# xiaozhi.net
KiCad netlist of a schematic drawn in EasyEDA Pro
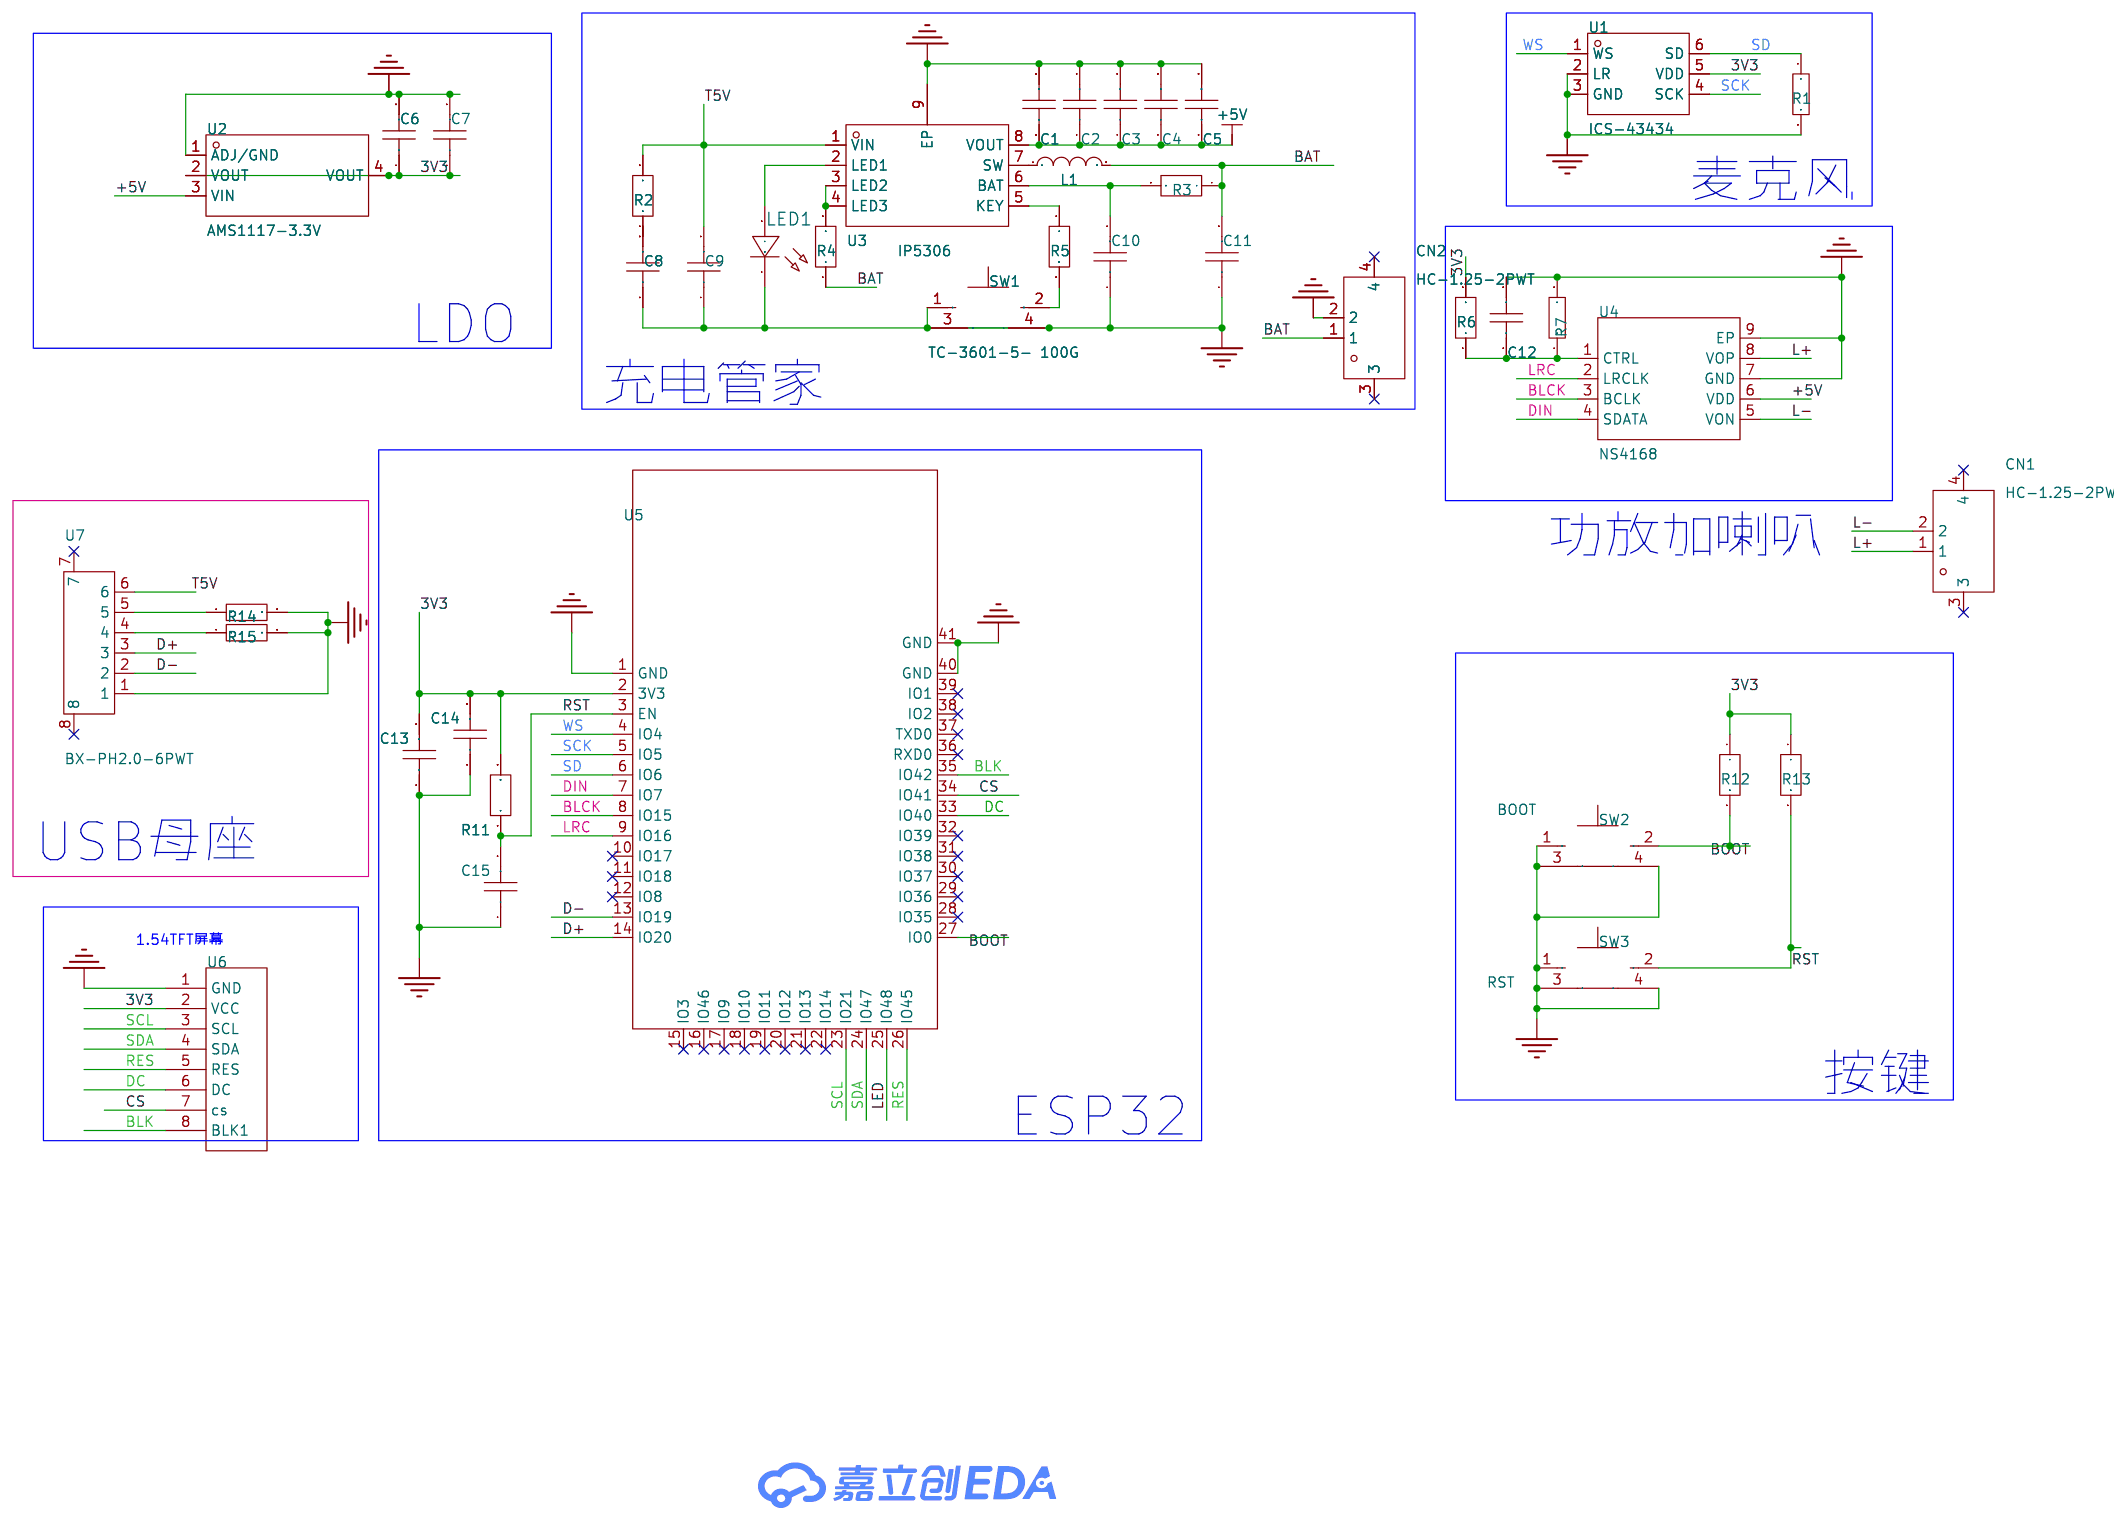
[diagram p0: schematic sheet]

(export (version "E")
  (design (tool "Eeschema 10.0.6"))
  (components
    (comp (ref "C1")
      (value "22UF")
      (footprint "easyedapro:C0603")
      (libsource (lib "easyedapro") (part "CapAcitance"))
    )
    (comp (ref "C2")
      (value "22UF")
      (footprint "easyedapro:C0603")
      (libsource (lib "easyedapro") (part "CapAcitance"))
    )
    (comp (ref "C3")
      (value "22UF")
      (footprint "easyedapro:C0603")
      (libsource (lib "easyedapro") (part "CapAcitance"))
    )
    (comp (ref "C4")
      (value "22UF")
      (footprint "easyedapro:C0603")
      (libsource (lib "easyedapro") (part "CapAcitance"))
    )
    (comp (ref "C5")
      (value "22UF")
      (footprint "easyedapro:C0603")
      (libsource (lib "easyedapro") (part "CapAcitance"))
    )
    (comp (ref "C6")
      (value "100NF")
      (footprint "easyedapro:C0603")
      (libsource (lib "easyedapro") (part "CapAcitance"))
    )
    (comp (ref "C7")
      (value "10UF")
      (footprint "easyedapro:C0603")
      (libsource (lib "easyedapro") (part "CapAcitance"))
    )
    (comp (ref "C8")
      (value "10uF")
      (footprint "easyedapro:C0805")
      (description "容值:10uF;精度:±10%;额定电压:25V;温度系数:X5R;")
      (fields
        (field (name "Manufacturer Part") "CGA0805X5R106K250MT")
        (field (name "Manufacturer") "HRE(芯声)")
      )
      (libsource (lib "easyedapro") (part "CGA0805X5R106K250MT"))
    )
    (comp (ref "C9")
      (value "10uF")
      (footprint "easyedapro:C0805")
      (description "容值:10uF;精度:±10%;额定电压:25V;温度系数:X5R;")
      (fields
        (field (name "Manufacturer Part") "CGA0805X5R106K250MT")
        (field (name "Manufacturer") "HRE(芯声)")
      )
      (libsource (lib "easyedapro") (part "CGA0805X5R106K250MT"))
    )
    (comp (ref "C10")
      (value "22UF")
      (footprint "easyedapro:C0603")
      (libsource (lib "easyedapro") (part "CapAcitance"))
    )
    (comp (ref "C11")
      (value "22UF")
      (footprint "easyedapro:C0603")
      (libsource (lib "easyedapro") (part "CapAcitance"))
    )
    (comp (ref "C12")
      (value "10UF")
      (footprint "easyedapro:C0603")
      (libsource (lib "easyedapro") (part "CapAcitance"))
    )
    (comp (ref "C13")
      (value "10uF")
      (footprint "easyedapro:C0805")
      (description "容值:10uF;精度:±10%;额定电压:25V;温度系数:X5R;")
      (fields
        (field (name "Manufacturer Part") "CGA0805X5R106K250MT")
        (field (name "Manufacturer") "HRE(芯声)")
      )
      (libsource (lib "easyedapro") (part "CGA0805X5R106K250MT"))
    )
    (comp (ref "C14")
      (value "100nF")
      (footprint "easyedapro:C0805")
      (description "容值:10uF;精度:±10%;额定电压:25V;温度系数:X5R;")
      (fields
        (field (name "Manufacturer Part") "CGA0805X5R106K250MT")
        (field (name "Manufacturer") "HRE(芯声)")
      )
      (libsource (lib "easyedapro") (part "CGA0805X5R106K250MT"))
    )
    (comp (ref "C15")
      (value "1uF")
      (footprint "easyedapro:C0805")
      (description "容值:10uF;精度:±10%;额定电压:25V;温度系数:X5R;")
      (fields
        (field (name "Manufacturer Part") "CGA0805X5R106K250MT")
        (field (name "Manufacturer") "HRE(芯声)")
      )
      (libsource (lib "easyedapro") (part "CGA0805X5R106K250MT"))
    )
    (comp (ref "CN1")
      (value "HC-1.25-2PWT")
      (footprint "easyedapro:CONN-SMD_2P-P1.25-HC-1.25-2PWT")
      (fields (field (name "Manufacturer") "HCTL(华灿天禄)"))
      (libsource (lib "easyedapro") (part "HC-1.25-2PWT"))
    )
    (comp (ref "CN2")
      (value "HC-1.25-2PWT")
      (footprint "easyedapro:CONN-SMD_2P-P1.25-HC-1.25-2PWT")
      (fields (field (name "Manufacturer") "HCTL(华灿天禄)"))
      (libsource (lib "easyedapro") (part "HC-1.25-2PWT"))
    )
    (comp (ref "L1")
      (value "1uH")
      (footprint "easyedapro:IND-SMD_L4.4-W4.2")
      (description "电感值:1uH;精度:±20%;饱和电流(Isat):7A;类型:一体成型电感;")
      (fields
        (field (name "Manufacturer Part") "CXP0420-1ROM-AG(1uh)")
        (field (name "Manufacturer") "DMBJ(振宝佳)")
      )
      (libsource (lib "easyedapro") (part "CXP0420-1ROM-AG(1UH)"))
    )
    (comp (ref "LED1")
      (value "~")
      (footprint "easyedapro:LED_0805")
      (libsource (lib "easyedapro") (part "LED_R"))
    )
    (comp (ref "R1") (value "100K") (footprint "easyedapro:R0805") (libsource (lib "easyedapro") (part "电阻")))
    (comp (ref "R2")
      (value "2R")
      (footprint "easyedapro:R0805")
      (description "电阻类型:厚膜电阻;阻值:500mΩ;精度:±5%;功率:125mW;最大工作电压:300V;温度系数:±300ppm/°C;")
      (fields (field (name "Manufacturer Part") "FRL0805JR500TS") (field (name "Manufacturer") "FOJAN(富捷)"))
      (libsource (lib "easyedapro") (part "FRL0805JR500TS"))
    )
    (comp (ref "R3")
      (value "500mΩ")
      (footprint "easyedapro:R0805")
      (description "电阻类型:厚膜电阻;阻值:500mΩ;精度:±5%;功率:125mW;最大工作电压:300V;温度系数:±300ppm/°C;")
      (fields (field (name "Manufacturer Part") "FRL0805JR500TS") (field (name "Manufacturer") "FOJAN(富捷)"))
      (libsource (lib "easyedapro") (part "FRL0805JR500TS"))
    )
    (comp (ref "R4")
      (value "1K")
      (footprint "easyedapro:R0805")
      (description "电阻类型:厚膜电阻;阻值:500mΩ;精度:±5%;功率:125mW;最大工作电压:300V;温度系数:±300ppm/°C;")
      (fields (field (name "Manufacturer Part") "FRL0805JR500TS") (field (name "Manufacturer") "FOJAN(富捷)"))
      (libsource (lib "easyedapro") (part "FRL0805JR500TS"))
    )
    (comp (ref "R5")
      (value "10K")
      (footprint "easyedapro:R0805")
      (description "电阻类型:厚膜电阻;阻值:500mΩ;精度:±5%;功率:125mW;最大工作电压:300V;温度系数:±300ppm/°C;")
      (fields (field (name "Manufacturer Part") "FRL0805JR500TS") (field (name "Manufacturer") "FOJAN(富捷)"))
      (libsource (lib "easyedapro") (part "FRL0805JR500TS"))
    )
    (comp (ref "R6")
      (value "10K")
      (footprint "easyedapro:R0805")
      (description "电阻类型:厚膜电阻;阻值:500mΩ;精度:±5%;功率:125mW;最大工作电压:300V;温度系数:±300ppm/°C;")
      (fields (field (name "Manufacturer Part") "FRL0805JR500TS") (field (name "Manufacturer") "FOJAN(富捷)"))
      (libsource (lib "easyedapro") (part "FRL0805JR500TS"))
    )
    (comp (ref "R7")
      (value "5.1kΩ")
      (footprint "easyedapro:R0805")
      (description "电阻类型:厚膜电阻;阻值:5.1kΩ;精度:±1%;功率:125mW;最大工作电压:150V;温度系数:±100ppm/℃;")
      (fields
        (field (name "Manufacturer Part") "0805W8F5101T5E")
        (field (name "Manufacturer") "UNI-ROYAL(厚声)")
      )
      (libsource (lib "easyedapro") (part "0805W8F5101T5E"))
    )
    (comp (ref "R11")
      (value "10K")
      (footprint "easyedapro:R0805")
      (description "电阻类型:厚膜电阻;阻值:500mΩ;精度:±5%;功率:125mW;最大工作电压:300V;温度系数:±300ppm/°C;")
      (fields (field (name "Manufacturer Part") "FRL0805JR500TS") (field (name "Manufacturer") "FOJAN(富捷)"))
      (libsource (lib "easyedapro") (part "FRL0805JR500TS"))
    )
    (comp (ref "R12")
      (value "10K")
      (footprint "easyedapro:R0805")
      (description "电阻类型:厚膜电阻;阻值:500mΩ;精度:±5%;功率:125mW;最大工作电压:300V;温度系数:±300ppm/°C;")
      (fields (field (name "Manufacturer Part") "FRL0805JR500TS") (field (name "Manufacturer") "FOJAN(富捷)"))
      (libsource (lib "easyedapro") (part "FRL0805JR500TS"))
    )
    (comp (ref "R13")
      (value "10K")
      (footprint "easyedapro:R0805")
      (description "电阻类型:厚膜电阻;阻值:500mΩ;精度:±5%;功率:125mW;最大工作电压:300V;温度系数:±300ppm/°C;")
      (fields (field (name "Manufacturer Part") "FRL0805JR500TS") (field (name "Manufacturer") "FOJAN(富捷)"))
      (libsource (lib "easyedapro") (part "FRL0805JR500TS"))
    )
    (comp (ref "R14")
      (value "5.1kΩ")
      (footprint "easyedapro:R0805")
      (description "电阻类型:厚膜电阻;阻值:5.1kΩ;精度:±1%;功率:125mW;最大工作电压:150V;温度系数:±100ppm/℃;")
      (fields
        (field (name "Manufacturer Part") "0805W8F5101T5E")
        (field (name "Manufacturer") "UNI-ROYAL(厚声)")
      )
      (libsource (lib "easyedapro") (part "0805W8F5101T5E"))
    )
    (comp (ref "R15")
      (value "5.1kΩ")
      (footprint "easyedapro:R0805")
      (description "电阻类型:厚膜电阻;阻值:5.1kΩ;精度:±1%;功率:125mW;最大工作电压:150V;温度系数:±100ppm/℃;")
      (fields
        (field (name "Manufacturer Part") "0805W8F5101T5E")
        (field (name "Manufacturer") "UNI-ROYAL(厚声)")
      )
      (libsource (lib "easyedapro") (part "0805W8F5101T5E"))
    )
    (comp (ref "SW1")
      (value "TC-3601-5- 100G")
      (footprint "easyedapro:KEY-TH_TC-3601-5-100G_1")
      (fields (field (name "Manufacturer") "HCTL(华灿天禄)"))
      (libsource (lib "easyedapro") (part "TC-3601-5- 100G"))
    )
    (comp (ref "SW2")
      (value "BOOT")
      (footprint "easyedapro:KEY-TH_TC-3601-5-100G_1")
      (fields (field (name "Manufacturer") "HCTL(华灿天禄)"))
      (libsource (lib "easyedapro") (part "TC-3601-5- 100G"))
    )
    (comp (ref "SW3")
      (value "RST")
      (footprint "easyedapro:KEY-TH_TC-3601-5-100G_1")
      (fields (field (name "Manufacturer") "HCTL(华灿天禄)"))
      (libsource (lib "easyedapro") (part "TC-3601-5- 100G"))
    )
    (comp (ref "U1")
      (value "ICS-43434")
      (footprint "easyedapro:MIC-SMD_6P-L3.5-W2.7-P0.90-BL")
      (description "指向性:全指向;信噪比:64dB;灵敏度:-;")
      (fields (field (name "Manufacturer") "TDK InvenSense(应美盛)"))
      (libsource (lib "easyedapro") (part "ICS-43434_C5656610"))
    )
    (comp (ref "U2")
      (value "AMS1117-3.3V")
      (footprint "easyedapro:SOT-223-4_L6.5-W3.5-P2.30-LS7.0-TR")
      (description "输出类型:固定;最大输入电压:18V;输出电压:3.3V;最大输出电流:1A;输出极性:正极;")
      (fields (field (name "Manufacturer") "MSKSEMI(美森科)"))
      (libsource (lib "easyedapro") (part "AMS1117-3.3V_C5120765"))
    )
    (comp (ref "U3")
      (value "IP5306")
      (footprint "easyedapro:ESOP-8_L4.9-W3.9-P1.27-LS6.0-BL-EP")
      (description "2.1A充电2.4A放电高集成度移动电源SOC")
      (fields (field (name "Manufacturer") "INJOINIC(英集芯)"))
      (libsource (lib "easyedapro") (part "IP5306"))
    )
    (comp (ref "U4")
      (value "NS4168")
      (footprint "easyedapro:ESOP-8_L4.9-W3.9-P1.27-LS6.0-BL-EP")
      (description "功放类型:D类功放;输出功率:2.5Wx1@4Ω;")
      (fields (field (name "Manufacturer") "Nsiway(纳芯威)"))
      (libsource (lib "easyedapro") (part "NS4168_C910588"))
    )
    (comp (ref "U5")
      (value "ESP32-S3-WROOM-1-N16R8")
      (footprint "easyedapro:WIRELM-SMD_ESP32-S3-WROOM-1")
      (fields (field (name "Manufacturer") "ESPRESSIF(乐鑫)"))
      (libsource (lib "easyedapro") (part "ESP32-S3-WROOM-1(N16R8)"))
    )
    (comp (ref "U6") (value "~") (libsource (lib "easyedapro") (part "TFT1.3液晶屏")))
    (comp (ref "U7")
      (value "BX-PH2.0-6PWT")
      (footprint "easyedapro:CONN-SMD_6P-P2.00_MXPH-2.0-6P-WT1-0-A")
      (fields (field (name "Manufacturer") "Bossie(博锡)"))
      (libsource (lib "easyedapro") (part "BX-PH2.0-6PWT"))
    )
  )
  (nets
    (net (code "1") (name "+5V") (class "Default")
      (node (ref "C1") (pin "1") (pinfunction "1_1") (pintype "input"))
      (node (ref "C2") (pin "1") (pinfunction "1_1") (pintype "input"))
      (node (ref "C3") (pin "1") (pinfunction "1_1") (pintype "input"))
      (node (ref "C4") (pin "1") (pinfunction "1_1") (pintype "input"))
      (node (ref "C5") (pin "1") (pinfunction "1_1") (pintype "input"))
      (node (ref "U2") (pin "3") (pinfunction "VIN_3") (pintype "unspecified"))
      (node (ref "U3") (pin "8") (pinfunction "VOUT_8") (pintype "unspecified"))
      (node (ref "U4") (pin "6") (pinfunction "VDD_6") (pintype "unspecified"))
    )
    (net (code "2") (name "/3V3") (class "Default")
      (node (ref "C13") (pin "2") (pinfunction "2_2") (pintype "unspecified"))
      (node (ref "C14") (pin "2") (pinfunction "2_2") (pintype "unspecified"))
      (node (ref "C6") (pin "1") (pinfunction "1_1") (pintype "input"))
      (node (ref "C7") (pin "1") (pinfunction "1_1") (pintype "input"))
      (node (ref "R11") (pin "2") (pinfunction "2_2") (pintype "unspecified"))
      (node (ref "R12") (pin "1") (pinfunction "1_1") (pintype "unspecified"))
      (node (ref "R13") (pin "1") (pinfunction "1_1") (pintype "unspecified"))
      (node (ref "R6") (pin "2") (pinfunction "2_2") (pintype "unspecified"))
      (node (ref "U1") (pin "5") (pinfunction "VDD_5") (pintype "unspecified"))
      (node (ref "U2") (pin "2") (pinfunction "VOUT_2") (pintype "unspecified"))
      (node (ref "U2") (pin "4") (pinfunction "VOUT_4") (pintype "unspecified"))
      (node (ref "U5") (pin "2") (pinfunction "3V3_2") (pintype "unspecified"))
      (node (ref "U6") (pin "2") (pinfunction "VCC_2") (pintype "input"))
    )
    (net (code "3") (name "/BAT") (class "Default")
      (node (ref "C11") (pin "2") (pinfunction "2_2") (pintype "input"))
      (node (ref "CN2") (pin "1") (pinfunction "1_1") (pintype "unspecified"))
      (node (ref "L1") (pin "2") (pinfunction "2_2") (pintype "unspecified"))
      (node (ref "R3") (pin "1") (pinfunction "1_1") (pintype "unspecified"))
      (node (ref "R4") (pin "1") (pinfunction "1_1") (pintype "unspecified"))
    )
    (net (code "4") (name "/BLCK") (class "Default")
      (node (ref "U4") (pin "3") (pinfunction "BCLK_3") (pintype "unspecified"))
      (node (ref "U5") (pin "8") (pinfunction "IO15_8") (pintype "unspecified"))
    )
    (net (code "5") (name "/BLK") (class "Default")
      (node (ref "U5") (pin "35") (pinfunction "IO42_35") (pintype "unspecified"))
      (node (ref "U6") (pin "8") (pinfunction "BLK1_8") (pintype "input"))
    )
    (net (code "6") (name "/BOOT") (class "Default")
      (node (ref "R12") (pin "2") (pinfunction "2_2") (pintype "unspecified"))
      (node (ref "SW2") (pin "2") (pinfunction "2_2") (pintype "input"))
      (node (ref "U5") (pin "27") (pinfunction "IO0_27") (pintype "unspecified"))
    )
    (net (code "7") (name "/CS") (class "Default")
      (node (ref "U5") (pin "34") (pinfunction "IO41_34") (pintype "unspecified"))
      (node (ref "U6") (pin "7") (pinfunction "cs_7") (pintype "input"))
    )
    (net (code "8") (name "/D+") (class "Default")
      (node (ref "U5") (pin "14") (pinfunction "IO20_14") (pintype "unspecified"))
      (node (ref "U7") (pin "3") (pinfunction "3_3") (pintype "unspecified"))
    )
    (net (code "9") (name "/D-") (class "Default")
      (node (ref "U5") (pin "13") (pinfunction "IO19_13") (pintype "unspecified"))
      (node (ref "U7") (pin "2") (pinfunction "2_2") (pintype "unspecified"))
    )
    (net (code "10") (name "/DC") (class "Default")
      (node (ref "U5") (pin "33") (pinfunction "IO40_33") (pintype "unspecified"))
      (node (ref "U6") (pin "6") (pinfunction "DC_6") (pintype "input"))
    )
    (net (code "11") (name "/DIN") (class "Default")
      (node (ref "U4") (pin "4") (pinfunction "SDATA_4") (pintype "unspecified"))
      (node (ref "U5") (pin "7") (pinfunction "IO7_7") (pintype "unspecified"))
    )
    (net (code "12") (name "/L+") (class "Default")
      (node (ref "CN1") (pin "1") (pinfunction "1_1") (pintype "unspecified"))
      (node (ref "U4") (pin "8") (pinfunction "VOP_8") (pintype "unspecified"))
    )
    (net (code "13") (name "/L-") (class "Default")
      (node (ref "CN1") (pin "2") (pinfunction "2_2") (pintype "unspecified"))
      (node (ref "U4") (pin "5") (pinfunction "VON_5") (pintype "unspecified"))
    )
    (net (code "14") (name "/LED") (class "Default")
      (node (ref "U5") (pin "25") (pinfunction "IO48_25") (pintype "unspecified"))
    )
    (net (code "15") (name "/LRC") (class "Default")
      (node (ref "U4") (pin "2") (pinfunction "LRCLK_2") (pintype "unspecified"))
      (node (ref "U5") (pin "9") (pinfunction "IO16_9") (pintype "unspecified"))
    )
    (net (code "16") (name "/RES") (class "Default")
      (node (ref "U5") (pin "26") (pinfunction "IO45_26") (pintype "unspecified"))
      (node (ref "U6") (pin "5") (pinfunction "RES_5") (pintype "input"))
    )
    (net (code "17") (name "/RST") (class "Default")
      (node (ref "C15") (pin "2") (pinfunction "2_2") (pintype "unspecified"))
      (node (ref "R11") (pin "1") (pinfunction "1_1") (pintype "unspecified"))
      (node (ref "R13") (pin "2") (pinfunction "2_2") (pintype "unspecified"))
      (node (ref "SW3") (pin "2") (pinfunction "2_2") (pintype "input"))
      (node (ref "U5") (pin "3") (pinfunction "EN_3") (pintype "unspecified"))
    )
    (net (code "18") (name "/SCK") (class "Default")
      (node (ref "U1") (pin "4") (pinfunction "SCK_4") (pintype "unspecified"))
      (node (ref "U5") (pin "5") (pinfunction "IO5_5") (pintype "unspecified"))
    )
    (net (code "19") (name "/SCL") (class "Default")
      (node (ref "U5") (pin "23") (pinfunction "IO21_23") (pintype "unspecified"))
      (node (ref "U6") (pin "3") (pinfunction "SCL_3") (pintype "input"))
    )
    (net (code "20") (name "/SD") (class "Default")
      (node (ref "R1") (pin "1") (pinfunction "1_1") (pintype "input"))
      (node (ref "U1") (pin "6") (pinfunction "SD_6") (pintype "unspecified"))
      (node (ref "U5") (pin "6") (pinfunction "IO6_6") (pintype "unspecified"))
    )
    (net (code "21") (name "/SDA") (class "Default")
      (node (ref "U5") (pin "24") (pinfunction "IO47_24") (pintype "unspecified"))
      (node (ref "U6") (pin "4") (pinfunction "SDA_4") (pintype "input"))
    )
    (net (code "22") (name "/T5V") (class "Default")
      (node (ref "C9") (pin "2") (pinfunction "2_2") (pintype "unspecified"))
      (node (ref "R2") (pin "2") (pinfunction "2_2") (pintype "unspecified"))
      (node (ref "U3") (pin "1") (pinfunction "VIN_1") (pintype "unspecified"))
      (node (ref "U7") (pin "6") (pinfunction "6_6") (pintype "unspecified"))
    )
    (net (code "23") (name "/WS") (class "Default")
      (node (ref "U1") (pin "1") (pinfunction "WS_1") (pintype "unspecified"))
      (node (ref "U5") (pin "4") (pinfunction "IO4_4") (pintype "unspecified"))
    )
    (net (code "24") (name "GND") (class "Default")
      (node (ref "C1") (pin "2") (pinfunction "2_2") (pintype "input"))
      (node (ref "C10") (pin "1") (pinfunction "1_1") (pintype "input"))
      (node (ref "C11") (pin "1") (pinfunction "1_1") (pintype "input"))
      (node (ref "C12") (pin "2") (pinfunction "2_2") (pintype "input"))
      (node (ref "C13") (pin "1") (pinfunction "1_1") (pintype "unspecified"))
      (node (ref "C14") (pin "1") (pinfunction "1_1") (pintype "unspecified"))
      (node (ref "C15") (pin "1") (pinfunction "1_1") (pintype "unspecified"))
      (node (ref "C2") (pin "2") (pinfunction "2_2") (pintype "input"))
      (node (ref "C3") (pin "2") (pinfunction "2_2") (pintype "input"))
      (node (ref "C4") (pin "2") (pinfunction "2_2") (pintype "input"))
      (node (ref "C5") (pin "2") (pinfunction "2_2") (pintype "input"))
      (node (ref "C6") (pin "2") (pinfunction "2_2") (pintype "input"))
      (node (ref "C7") (pin "2") (pinfunction "2_2") (pintype "input"))
      (node (ref "C8") (pin "1") (pinfunction "1_1") (pintype "unspecified"))
      (node (ref "C9") (pin "1") (pinfunction "1_1") (pintype "unspecified"))
      (node (ref "CN2") (pin "2") (pinfunction "2_2") (pintype "unspecified"))
      (node (ref "LED1") (pin "1") (pinfunction "C_1") (pintype "input"))
      (node (ref "R1") (pin "2") (pinfunction "2_2") (pintype "input"))
      (node (ref "R14") (pin "2") (pinfunction "2_2") (pintype "input"))
      (node (ref "R15") (pin "2") (pinfunction "2_2") (pintype "input"))
      (node (ref "R7") (pin "2") (pinfunction "2_2") (pintype "input"))
      (node (ref "SW1") (pin "1") (pinfunction "1_1") (pintype "input"))
      (node (ref "SW1") (pin "3") (pinfunction "3_3") (pintype "unspecified"))
      (node (ref "SW1") (pin "4") (pinfunction "4_4") (pintype "unspecified"))
      (node (ref "SW2") (pin "1") (pinfunction "1_1") (pintype "input"))
      (node (ref "SW2") (pin "3") (pinfunction "3_3") (pintype "unspecified"))
      (node (ref "SW2") (pin "4") (pinfunction "4_4") (pintype "unspecified"))
      (node (ref "SW3") (pin "1") (pinfunction "1_1") (pintype "input"))
      (node (ref "SW3") (pin "3") (pinfunction "3_3") (pintype "unspecified"))
      (node (ref "SW3") (pin "4") (pinfunction "4_4") (pintype "unspecified"))
      (node (ref "U1") (pin "2") (pinfunction "LR_2") (pintype "unspecified"))
      (node (ref "U1") (pin "3") (pinfunction "GND_3") (pintype "unspecified"))
      (node (ref "U2") (pin "1") (pinfunction "ADJ/GND_1") (pintype "unspecified"))
      (node (ref "U3") (pin "9") (pinfunction "EP_9") (pintype "unspecified"))
      (node (ref "U4") (pin "7") (pinfunction "GND_7") (pintype "unspecified"))
      (node (ref "U4") (pin "9") (pinfunction "EP_9") (pintype "unspecified"))
      (node (ref "U5") (pin "1") (pinfunction "GND_1") (pintype "unspecified"))
      (node (ref "U5") (pin "40") (pinfunction "GND_40") (pintype "unspecified"))
      (node (ref "U5") (pin "41") (pinfunction "GND_41") (pintype "unspecified"))
      (node (ref "U6") (pin "1") (pinfunction "GND_1") (pintype "input"))
      (node (ref "U7") (pin "1") (pinfunction "1_1") (pintype "unspecified"))
    )
    (net (code "25") (name "Net-(C8-Pad2)") (class "Default")
      (node (ref "C8") (pin "2") (pinfunction "2_2") (pintype "unspecified"))
      (node (ref "R2") (pin "1") (pinfunction "1_1") (pintype "unspecified"))
    )
    (net (code "26") (name "Net-(LED1-A)") (class "Default")
      (node (ref "LED1") (pin "2") (pinfunction "A_2") (pintype "input"))
      (node (ref "U3") (pin "2") (pinfunction "LED1_2") (pintype "unspecified"))
    )
    (net (code "27") (name "Net-(R5-Pad2)") (class "Default")
      (node (ref "R5") (pin "2") (pinfunction "2_2") (pintype "unspecified"))
      (node (ref "SW1") (pin "2") (pinfunction "2_2") (pintype "input"))
    )
    (net (code "28") (name "Net-(R14-Pad1)") (class "Default")
      (node (ref "R14") (pin "1") (pinfunction "1_1") (pintype "input"))
      (node (ref "U7") (pin "5") (pinfunction "5_5") (pintype "unspecified"))
    )
    (net (code "29") (name "Net-(R15-Pad1)") (class "Default")
      (node (ref "R15") (pin "1") (pinfunction "1_1") (pintype "input"))
      (node (ref "U7") (pin "4") (pinfunction "4_4") (pintype "unspecified"))
    )
    (net (code "30") (name "Net-(U3-BAT)") (class "Default")
      (node (ref "C10") (pin "2") (pinfunction "2_2") (pintype "input"))
      (node (ref "R3") (pin "2") (pinfunction "2_2") (pintype "unspecified"))
      (node (ref "U3") (pin "6") (pinfunction "BAT_6") (pintype "unspecified"))
    )
    (net (code "31") (name "Net-(U3-KEY)") (class "Default")
      (node (ref "R5") (pin "1") (pinfunction "1_1") (pintype "unspecified"))
      (node (ref "U3") (pin "5") (pinfunction "KEY_5") (pintype "unspecified"))
    )
    (net (code "32") (name "Net-(U3-LED2)") (class "Default")
      (node (ref "R4") (pin "2") (pinfunction "2_2") (pintype "unspecified"))
      (node (ref "U3") (pin "3") (pinfunction "LED2_3") (pintype "unspecified"))
      (node (ref "U3") (pin "4") (pinfunction "LED3_4") (pintype "unspecified"))
    )
    (net (code "33") (name "Net-(U3-SW)") (class "Default")
      (node (ref "L1") (pin "1") (pinfunction "1_1") (pintype "unspecified"))
      (node (ref "U3") (pin "7") (pinfunction "SW_7") (pintype "unspecified"))
    )
    (net (code "34") (name "Net-(U4-CTRL)") (class "Default")
      (node (ref "C12") (pin "1") (pinfunction "1_1") (pintype "input"))
      (node (ref "R6") (pin "1") (pinfunction "1_1") (pintype "unspecified"))
      (node (ref "R7") (pin "1") (pinfunction "1_1") (pintype "input"))
      (node (ref "U4") (pin "1") (pinfunction "CTRL_1") (pintype "unspecified"))
    )
    (net (code "35") (name "unconnected-(CN1-Pad3)") (class "Default")
      (node (ref "CN1") (pin "3") (pinfunction "3_3") (pintype "unspecified+no_connect"))
    )
    (net (code "36") (name "unconnected-(CN1-Pad4)") (class "Default")
      (node (ref "CN1") (pin "4") (pinfunction "4_4") (pintype "unspecified+no_connect"))
    )
    (net (code "37") (name "unconnected-(CN2-Pad3)") (class "Default")
      (node (ref "CN2") (pin "3") (pinfunction "3_3") (pintype "unspecified+no_connect"))
    )
    (net (code "38") (name "unconnected-(CN2-Pad4)") (class "Default")
      (node (ref "CN2") (pin "4") (pinfunction "4_4") (pintype "unspecified+no_connect"))
    )
    (net (code "39") (name "unconnected-(U5-IO1-Pad39)") (class "Default")
      (node (ref "U5") (pin "39") (pinfunction "IO1_39") (pintype "unspecified+no_connect"))
    )
    (net (code "40") (name "unconnected-(U5-IO2-Pad38)") (class "Default")
      (node (ref "U5") (pin "38") (pinfunction "IO2_38") (pintype "unspecified+no_connect"))
    )
    (net (code "41") (name "unconnected-(U5-IO3-Pad15)") (class "Default")
      (node (ref "U5") (pin "15") (pinfunction "IO3_15") (pintype "unspecified+no_connect"))
    )
    (net (code "42") (name "unconnected-(U5-IO8-Pad12)") (class "Default")
      (node (ref "U5") (pin "12") (pinfunction "IO8_12") (pintype "unspecified+no_connect"))
    )
    (net (code "43") (name "unconnected-(U5-IO9-Pad17)") (class "Default")
      (node (ref "U5") (pin "17") (pinfunction "IO9_17") (pintype "unspecified+no_connect"))
    )
    (net (code "44") (name "unconnected-(U5-IO10-Pad18)") (class "Default")
      (node (ref "U5") (pin "18") (pinfunction "IO10_18") (pintype "unspecified+no_connect"))
    )
    (net (code "45") (name "unconnected-(U5-IO11-Pad19)") (class "Default")
      (node (ref "U5") (pin "19") (pinfunction "IO11_19") (pintype "unspecified+no_connect"))
    )
    (net (code "46") (name "unconnected-(U5-IO12-Pad20)") (class "Default")
      (node (ref "U5") (pin "20") (pinfunction "IO12_20") (pintype "unspecified+no_connect"))
    )
    (net (code "47") (name "unconnected-(U5-IO13-Pad21)") (class "Default")
      (node (ref "U5") (pin "21") (pinfunction "IO13_21") (pintype "unspecified+no_connect"))
    )
    (net (code "48") (name "unconnected-(U5-IO14-Pad22)") (class "Default")
      (node (ref "U5") (pin "22") (pinfunction "IO14_22") (pintype "unspecified+no_connect"))
    )
    (net (code "49") (name "unconnected-(U5-IO17-Pad10)") (class "Default")
      (node (ref "U5") (pin "10") (pinfunction "IO17_10") (pintype "unspecified+no_connect"))
    )
    (net (code "50") (name "unconnected-(U5-IO18-Pad11)") (class "Default")
      (node (ref "U5") (pin "11") (pinfunction "IO18_11") (pintype "unspecified+no_connect"))
    )
    (net (code "51") (name "unconnected-(U5-IO35-Pad28)") (class "Default")
      (node (ref "U5") (pin "28") (pinfunction "IO35_28") (pintype "unspecified+no_connect"))
    )
    (net (code "52") (name "unconnected-(U5-IO36-Pad29)") (class "Default")
      (node (ref "U5") (pin "29") (pinfunction "IO36_29") (pintype "unspecified+no_connect"))
    )
    (net (code "53") (name "unconnected-(U5-IO37-Pad30)") (class "Default")
      (node (ref "U5") (pin "30") (pinfunction "IO37_30") (pintype "unspecified+no_connect"))
    )
    (net (code "54") (name "unconnected-(U5-IO38-Pad31)") (class "Default")
      (node (ref "U5") (pin "31") (pinfunction "IO38_31") (pintype "unspecified+no_connect"))
    )
    (net (code "55") (name "unconnected-(U5-IO39-Pad32)") (class "Default")
      (node (ref "U5") (pin "32") (pinfunction "IO39_32") (pintype "unspecified+no_connect"))
    )
    (net (code "56") (name "unconnected-(U5-IO46-Pad16)") (class "Default")
      (node (ref "U5") (pin "16") (pinfunction "IO46_16") (pintype "unspecified+no_connect"))
    )
    (net (code "57") (name "unconnected-(U5-RXD0-Pad36)") (class "Default")
      (node (ref "U5") (pin "36") (pinfunction "RXD0_36") (pintype "unspecified+no_connect"))
    )
    (net (code "58") (name "unconnected-(U5-TXD0-Pad37)") (class "Default")
      (node (ref "U5") (pin "37") (pinfunction "TXD0_37") (pintype "unspecified+no_connect"))
    )
    (net (code "59") (name "unconnected-(U7-Pad7)") (class "Default")
      (node (ref "U7") (pin "7") (pinfunction "7_7") (pintype "unspecified+no_connect"))
    )
    (net (code "60") (name "unconnected-(U7-Pad8)") (class "Default")
      (node (ref "U7") (pin "8") (pinfunction "8_8") (pintype "unspecified+no_connect"))
    )
  )
)
